# SparkFun_Qwiic_ADXL313.net
KiCad netlist of a schematic drawn in EAGLE
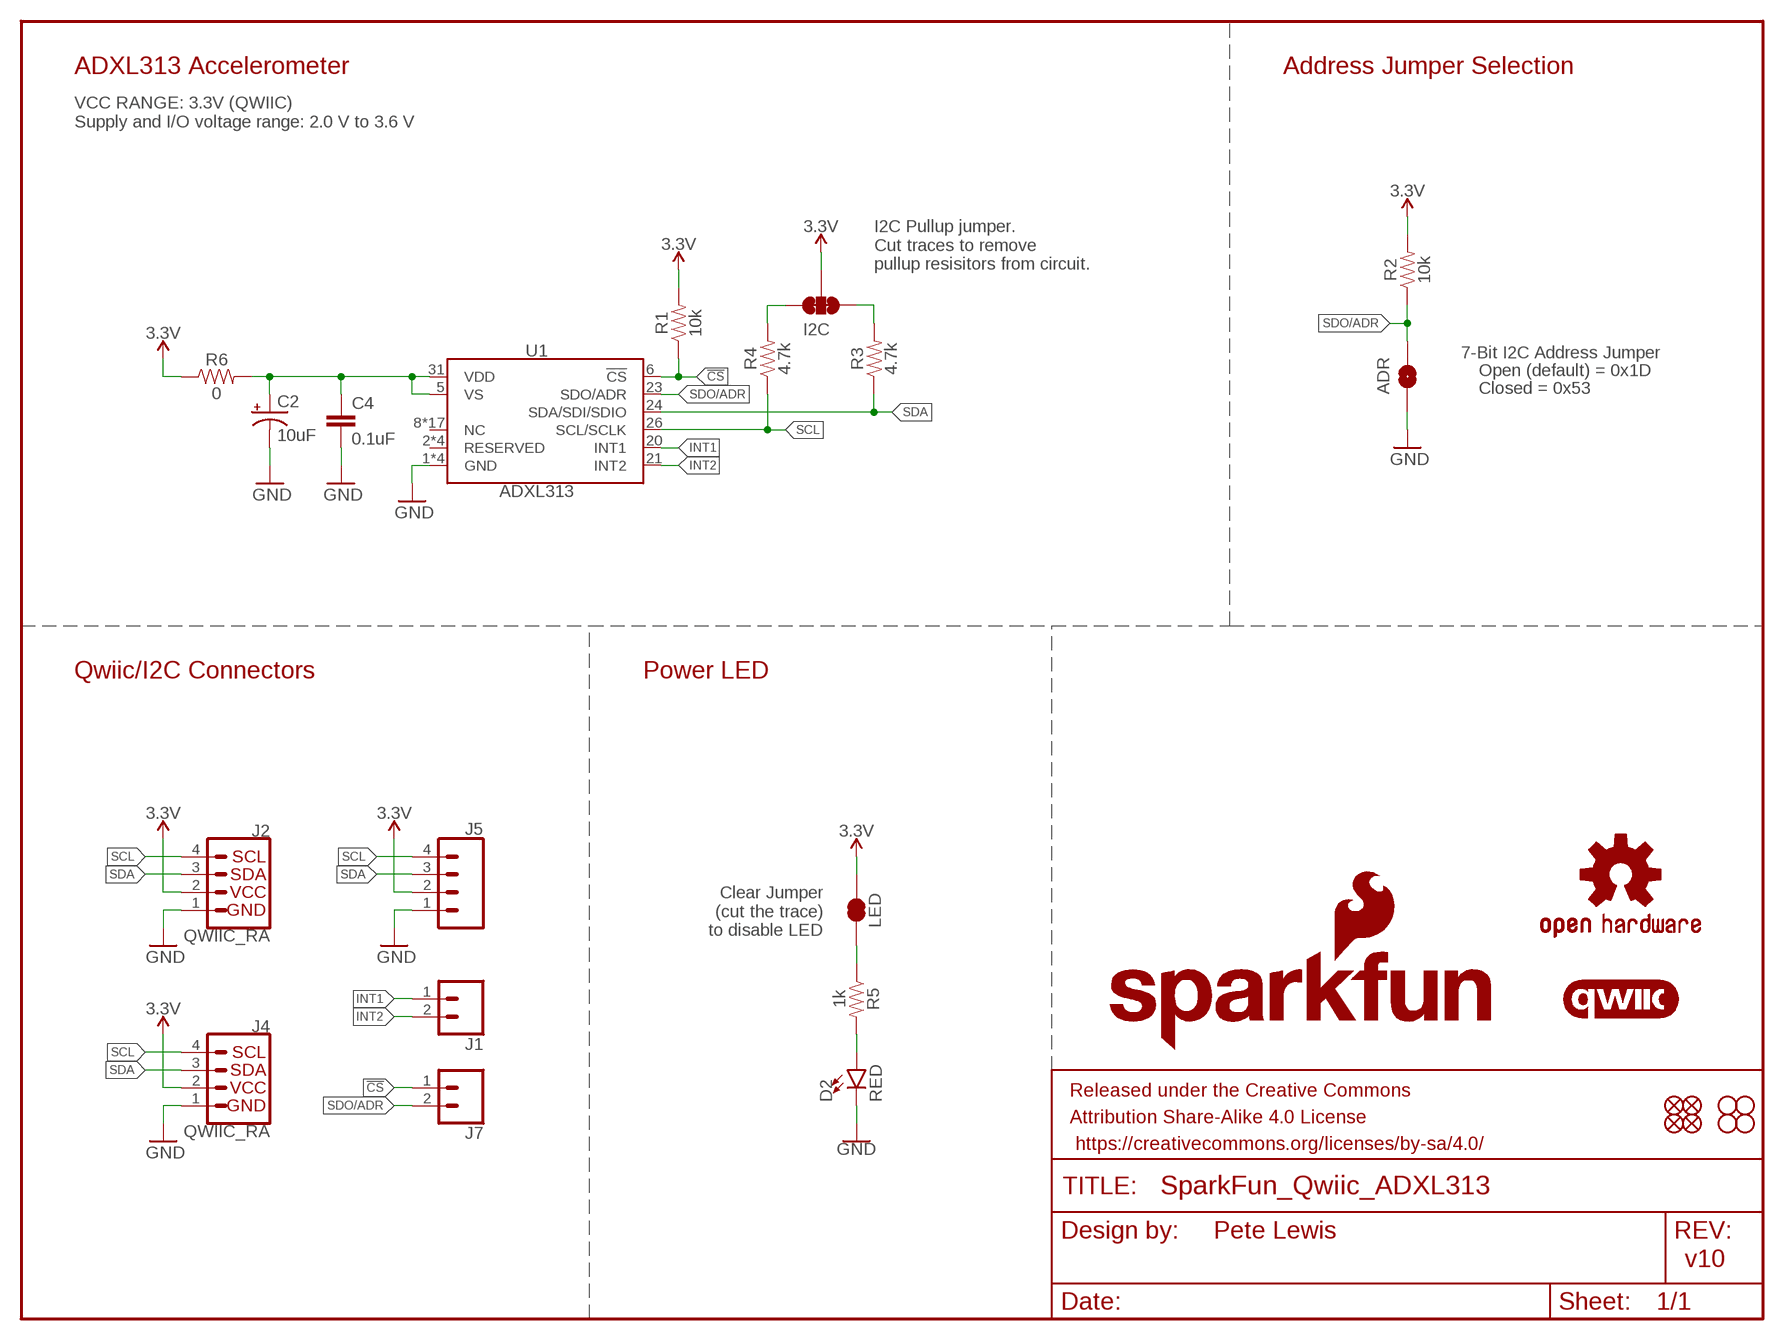
[diagram p0: schematic, sheet 1]

(export (version "E")
  (design (tool "Eeschema 10.0.6"))
  (components
    (comp (ref "ADR")
      (value "JUMPER-SMT_2_NO_SILK")
      (footprint "eagle-import:SMT-JUMPER_2_NO_SILK")
      (libsource (lib "eagle-import") (part "JUMPER-SMT_2_NO_SILK"))
    )
    (comp (ref "C2")
      (value "10uF")
      (footprint "eagle-import:EIA3216")
      (libsource (lib "eagle-import") (part "10UF-TANT"))
    )
    (comp (ref "C4")
      (value "0.1uF")
      (footprint "eagle-import:0603")
      (libsource (lib "eagle-import") (part "0.1UF-0603-25V-(+80/-20%)"))
    )
    (comp (ref "D2")
      (value "RED")
      (footprint "eagle-import:LED-0603")
      (libsource (lib "eagle-import") (part "LED-RED0603"))
    )
    (comp (ref "FRAME1")
      (value "FRAME-LETTER")
      (footprint "eagle-import:CREATIVE_COMMONS")
      (libsource (lib "eagle-import") (part "FRAME-LETTER"))
    )
    (comp (ref "I2C")
      (value "JUMPER-SMT_3_2-NC_TRACE_SILK")
      (footprint "eagle-import:SMT-JUMPER_3_2-NC_TRACE_SILK")
      (libsource (lib "eagle-import") (part "JUMPER-SMT_3_2-NC_TRACE_SILK"))
    )
    (comp (ref "J1")
      (value "CONN_021X02_NO_SILK")
      (footprint "eagle-import:1X02_NO_SILK")
      (libsource (lib "eagle-import") (part "CONN_021X02_NO_SILK"))
    )
    (comp (ref "J2")
      (value "QWIIC_RA")
      (footprint "eagle-import:JST04_1MM_RA")
      (libsource (lib "eagle-import") (part "QWIIC_CONNECTORJS-1MM"))
    )
    (comp (ref "J4")
      (value "QWIIC_RA")
      (footprint "eagle-import:JST04_1MM_RA")
      (libsource (lib "eagle-import") (part "QWIIC_CONNECTORJS-1MM"))
    )
    (comp (ref "J5")
      (value "CONN_041X04_NO_SILK")
      (footprint "eagle-import:1X04_NO_SILK")
      (libsource (lib "eagle-import") (part "CONN_041X04_NO_SILK"))
    )
    (comp (ref "J7")
      (value "CONN_021X02_NO_SILK")
      (footprint "eagle-import:1X02_NO_SILK")
      (libsource (lib "eagle-import") (part "CONN_021X02_NO_SILK"))
    )
    (comp (ref "JP1")
      (value "LED")
      (footprint "eagle-import:SMT-JUMPER_2_NC_TRACE_SILK")
      (libsource (lib "eagle-import") (part "JUMPER-SMT_2_NC_TRACE_SILK"))
    )
    (comp (ref "JP2")
      (value "FIDUCIALUFIDUCIAL")
      (footprint "eagle-import:MICRO-FIDUCIAL")
      (libsource (lib "eagle-import") (part "FIDUCIALUFIDUCIAL"))
    )
    (comp (ref "JP3")
      (value "STAND-OFF")
      (footprint "eagle-import:STAND-OFF")
      (libsource (lib "eagle-import") (part "STAND-OFF"))
    )
    (comp (ref "JP4")
      (value "STAND-OFF")
      (footprint "eagle-import:STAND-OFF")
      (libsource (lib "eagle-import") (part "STAND-OFF"))
    )
    (comp (ref "JP5")
      (value "FIDUCIALUFIDUCIAL")
      (footprint "eagle-import:MICRO-FIDUCIAL")
      (libsource (lib "eagle-import") (part "FIDUCIALUFIDUCIAL"))
    )
    (comp (ref "JP6")
      (value "FIDUCIALUFIDUCIAL")
      (footprint "eagle-import:MICRO-FIDUCIAL")
      (libsource (lib "eagle-import") (part "FIDUCIALUFIDUCIAL"))
    )
    (comp (ref "JP8")
      (value "STAND-OFF")
      (footprint "eagle-import:STAND-OFF")
      (libsource (lib "eagle-import") (part "STAND-OFF"))
    )
    (comp (ref "JP9")
      (value "STAND-OFF")
      (footprint "eagle-import:STAND-OFF")
      (libsource (lib "eagle-import") (part "STAND-OFF"))
    )
    (comp (ref "JP11")
      (value "FIDUCIALUFIDUCIAL")
      (footprint "eagle-import:MICRO-FIDUCIAL")
      (libsource (lib "eagle-import") (part "FIDUCIALUFIDUCIAL"))
    )
    (comp (ref "LOGO1")
      (value "OSHW-LOGOMINI")
      (footprint "eagle-import:OSHW-LOGO-MINI")
      (libsource (lib "eagle-import") (part "OSHW-LOGOMINI"))
    )
    (comp (ref "LOGO2")
      (value "SFE_LOGO_NAME_FLAME.1_INCH")
      (footprint "eagle-import:SFE_LOGO_NAME_FLAME_.1")
      (libsource (lib "eagle-import") (part "SFE_LOGO_NAME_FLAME.1_INCH"))
    )
    (comp (ref "LOGO3")
      (value "SFE_LOGO_FLAME.1_INCH")
      (footprint "eagle-import:SFE_LOGO_FLAME_.1")
      (libsource (lib "eagle-import") (part "SFE_LOGO_FLAME.1_INCH"))
    )
    (comp (ref "LOGO4")
      (value "QWIIC_LOGO_5MM")
      (footprint "eagle-import:QWIIC_5MM")
      (libsource (lib "eagle-import") (part "QWIIC_LOGO_5MM"))
    )
    (comp (ref "R1")
      (value "10k")
      (footprint "eagle-import:0603")
      (libsource (lib "eagle-import") (part "10KOHM-0603-1/10W-1%"))
    )
    (comp (ref "R2")
      (value "10k")
      (footprint "eagle-import:0603")
      (libsource (lib "eagle-import") (part "10KOHM-0603-1/10W-1%"))
    )
    (comp (ref "R3")
      (value "4.7k")
      (footprint "eagle-import:0603")
      (libsource (lib "eagle-import") (part "4.7KOHM-0603-1/10W-1%"))
    )
    (comp (ref "R4")
      (value "4.7k")
      (footprint "eagle-import:0603")
      (libsource (lib "eagle-import") (part "4.7KOHM-0603-1/10W-1%"))
    )
    (comp (ref "R5")
      (value "1k")
      (footprint "eagle-import:0603")
      (libsource (lib "eagle-import") (part "1KOHM-0603-1/10W-1%"))
    )
    (comp (ref "R6")
      (value "0")
      (footprint "eagle-import:0603")
      (libsource (lib "eagle-import") (part "0OHM-0603-1/10W"))
    )
    (comp (ref "U1")
      (value "ADXL313")
      (footprint "eagle-import:LFCSP")
      (libsource (lib "eagle-import") (part "ADXL313"))
    )
  )
  (nets
    (net (code "1") (name "/~{CS}") (class "Default")
      (node (ref "J7") (pin "1") (pinfunction "1_1") (pintype "passive"))
      (node (ref "R1") (pin "1") (pinfunction "1_1") (pintype "passive"))
      (node (ref "U1") (pin "6") (pinfunction "~{CS}_6") (pintype "bidirectional"))
    )
    (net (code "2") (name "3.3V") (class "Default")
      (node (ref "I2C") (pin "2") (pinfunction "2_2") (pintype "passive"))
      (node (ref "J2") (pin "2") (pinfunction "2_2") (pintype "power_in"))
      (node (ref "J4") (pin "2") (pinfunction "2_2") (pintype "power_in"))
      (node (ref "J5") (pin "2") (pinfunction "2_2") (pintype "passive"))
      (node (ref "JP1") (pin "2") (pinfunction "2_2") (pintype "passive"))
      (node (ref "R1") (pin "2") (pinfunction "2_2") (pintype "passive"))
      (node (ref "R2") (pin "2") (pinfunction "2_2") (pintype "passive"))
      (node (ref "R6") (pin "1") (pinfunction "1_1") (pintype "passive"))
    )
    (net (code "3") (name "GND") (class "Default")
      (node (ref "ADR") (pin "1") (pinfunction "1_1") (pintype "passive"))
      (node (ref "C2") (pin "C") (pinfunction "-_C") (pintype "passive"))
      (node (ref "C4") (pin "2") (pinfunction "2_2") (pintype "passive"))
      (node (ref "D2") (pin "C") (pinfunction "C_C") (pintype "passive"))
      (node (ref "J2") (pin "1") (pinfunction "1_1") (pintype "power_in"))
      (node (ref "J4") (pin "1") (pinfunction "1_1") (pintype "power_in"))
      (node (ref "J5") (pin "1") (pinfunction "1_1") (pintype "passive"))
      (node (ref "U1") (pin "1") (pinfunction "GND_1") (pintype "bidirectional"))
      (node (ref "U1") (pin "3") (pinfunction "GND_3") (pintype "bidirectional"))
      (node (ref "U1") (pin "4") (pinfunction "GND_4") (pintype "bidirectional"))
      (node (ref "U1") (pin "EPAD") (pinfunction "GND_EPAD") (pintype "bidirectional"))
    )
    (net (code "4") (name "INT1") (class "Default")
      (node (ref "J1") (pin "1") (pinfunction "1_1") (pintype "passive"))
      (node (ref "U1") (pin "20") (pinfunction "INT1_20") (pintype "bidirectional"))
    )
    (net (code "5") (name "INT2") (class "Default")
      (node (ref "J1") (pin "2") (pinfunction "2_2") (pintype "passive"))
      (node (ref "U1") (pin "21") (pinfunction "INT2_21") (pintype "bidirectional"))
    )
    (net (code "6") (name "Net-(C2-+)") (class "Default")
      (node (ref "C2") (pin "A") (pinfunction "+_A") (pintype "passive"))
      (node (ref "C4") (pin "1") (pinfunction "1_1") (pintype "passive"))
      (node (ref "R6") (pin "2") (pinfunction "2_2") (pintype "passive"))
      (node (ref "U1") (pin "31") (pinfunction "VDD_31") (pintype "bidirectional"))
      (node (ref "U1") (pin "5") (pinfunction "VS_5") (pintype "bidirectional"))
    )
    (net (code "7") (name "Net-(D2-PadA)") (class "Default")
      (node (ref "D2") (pin "A") (pinfunction "A_A") (pintype "passive"))
      (node (ref "R5") (pin "2") (pinfunction "2_2") (pintype "passive"))
    )
    (net (code "8") (name "Net-(I2C-Pad1)") (class "Default")
      (node (ref "I2C") (pin "1") (pinfunction "1_1") (pintype "passive"))
      (node (ref "R3") (pin "2") (pinfunction "2_2") (pintype "passive"))
    )
    (net (code "9") (name "Net-(I2C-Pad3)") (class "Default")
      (node (ref "I2C") (pin "3") (pinfunction "3_3") (pintype "passive"))
      (node (ref "R4") (pin "2") (pinfunction "2_2") (pintype "passive"))
    )
    (net (code "10") (name "Net-(JP1-Pad1)") (class "Default")
      (node (ref "JP1") (pin "1") (pinfunction "1_1") (pintype "passive"))
      (node (ref "R5") (pin "1") (pinfunction "1_1") (pintype "passive"))
    )
    (net (code "11") (name "SCL") (class "Default")
      (node (ref "J2") (pin "4") (pinfunction "4_4") (pintype "passive"))
      (node (ref "J4") (pin "4") (pinfunction "4_4") (pintype "passive"))
      (node (ref "J5") (pin "4") (pinfunction "4_4") (pintype "passive"))
      (node (ref "R4") (pin "1") (pinfunction "1_1") (pintype "passive"))
      (node (ref "U1") (pin "26") (pinfunction "SCL/SCLK_26") (pintype "bidirectional"))
    )
    (net (code "12") (name "SDA") (class "Default")
      (node (ref "J2") (pin "3") (pinfunction "3_3") (pintype "passive"))
      (node (ref "J4") (pin "3") (pinfunction "3_3") (pintype "passive"))
      (node (ref "J5") (pin "3") (pinfunction "3_3") (pintype "passive"))
      (node (ref "R3") (pin "1") (pinfunction "1_1") (pintype "passive"))
      (node (ref "U1") (pin "24") (pinfunction "SDA/SDI/SDIO_24") (pintype "bidirectional"))
    )
    (net (code "13") (name "SDO{slash}ADR") (class "Default")
      (node (ref "ADR") (pin "2") (pinfunction "2_2") (pintype "passive"))
      (node (ref "J7") (pin "2") (pinfunction "2_2") (pintype "passive"))
      (node (ref "R2") (pin "1") (pinfunction "1_1") (pintype "passive"))
      (node (ref "U1") (pin "23") (pinfunction "SDO/ADR_23") (pintype "bidirectional"))
    )
    (net (code "14") (name "unconnected-(U1-NC-Pad8)") (class "Default")
      (node (ref "U1") (pin "8") (pinfunction "NC_8") (pintype "no_connect"))
    )
    (net (code "15") (name "unconnected-(U1-NC-Pad9)") (class "Default")
      (node (ref "U1") (pin "9") (pinfunction "NC_9") (pintype "no_connect"))
    )
    (net (code "16") (name "unconnected-(U1-NC-Pad10)") (class "Default")
      (node (ref "U1") (pin "10") (pinfunction "NC_10") (pintype "no_connect"))
    )
    (net (code "17") (name "unconnected-(U1-NC-Pad11)") (class "Default")
      (node (ref "U1") (pin "11") (pinfunction "NC_11") (pintype "no_connect"))
    )
    (net (code "18") (name "unconnected-(U1-NC-Pad12)") (class "Default")
      (node (ref "U1") (pin "12") (pinfunction "NC_12") (pintype "no_connect"))
    )
    (net (code "19") (name "unconnected-(U1-NC-Pad13)") (class "Default")
      (node (ref "U1") (pin "13") (pinfunction "NC_13") (pintype "no_connect"))
    )
    (net (code "20") (name "unconnected-(U1-NC-Pad14)") (class "Default")
      (node (ref "U1") (pin "14") (pinfunction "NC_14") (pintype "no_connect"))
    )
    (net (code "21") (name "unconnected-(U1-NC-Pad15)") (class "Default")
      (node (ref "U1") (pin "15") (pinfunction "NC_15") (pintype "no_connect"))
    )
    (net (code "22") (name "unconnected-(U1-NC-Pad16)") (class "Default")
      (node (ref "U1") (pin "16") (pinfunction "NC_16") (pintype "no_connect"))
    )
    (net (code "23") (name "unconnected-(U1-NC-Pad17)") (class "Default")
      (node (ref "U1") (pin "17") (pinfunction "NC_17") (pintype "no_connect"))
    )
    (net (code "24") (name "unconnected-(U1-NC-Pad18)") (class "Default")
      (node (ref "U1") (pin "18") (pinfunction "NC_18") (pintype "no_connect"))
    )
    (net (code "25") (name "unconnected-(U1-NC-Pad19)") (class "Default")
      (node (ref "U1") (pin "19") (pinfunction "NC_19") (pintype "no_connect"))
    )
    (net (code "26") (name "unconnected-(U1-NC-Pad25)") (class "Default")
      (node (ref "U1") (pin "25") (pinfunction "NC_25") (pintype "no_connect"))
    )
    (net (code "27") (name "unconnected-(U1-NC-Pad27)") (class "Default")
      (node (ref "U1") (pin "27") (pinfunction "NC_27") (pintype "no_connect"))
    )
    (net (code "28") (name "unconnected-(U1-NC-Pad28)") (class "Default")
      (node (ref "U1") (pin "28") (pinfunction "NC_28") (pintype "no_connect"))
    )
    (net (code "29") (name "unconnected-(U1-NC-Pad29)") (class "Default")
      (node (ref "U1") (pin "29") (pinfunction "NC_29") (pintype "no_connect"))
    )
    (net (code "30") (name "unconnected-(U1-NC-Pad30)") (class "Default")
      (node (ref "U1") (pin "30") (pinfunction "NC_30") (pintype "no_connect"))
    )
    (net (code "31") (name "unconnected-(U1-RESERVED-Pad2)") (class "Default")
      (node (ref "U1") (pin "2") (pinfunction "RESERVED_2") (pintype "no_connect"))
    )
    (net (code "32") (name "unconnected-(U1-RESERVED-Pad7)") (class "Default")
      (node (ref "U1") (pin "7") (pinfunction "RESERVED_7") (pintype "no_connect"))
    )
    (net (code "33") (name "unconnected-(U1-RESERVED-Pad22)") (class "Default")
      (node (ref "U1") (pin "22") (pinfunction "RESERVED_22") (pintype "no_connect"))
    )
    (net (code "34") (name "unconnected-(U1-RESERVED-Pad32)") (class "Default")
      (node (ref "U1") (pin "32") (pinfunction "RESERVED_32") (pintype "no_connect"))
    )
  )
)
